# SCH_CheetahSpeedometer-Matt-Lin_2024-07-.net
KiCad netlist of a schematic drawn in EasyEDA
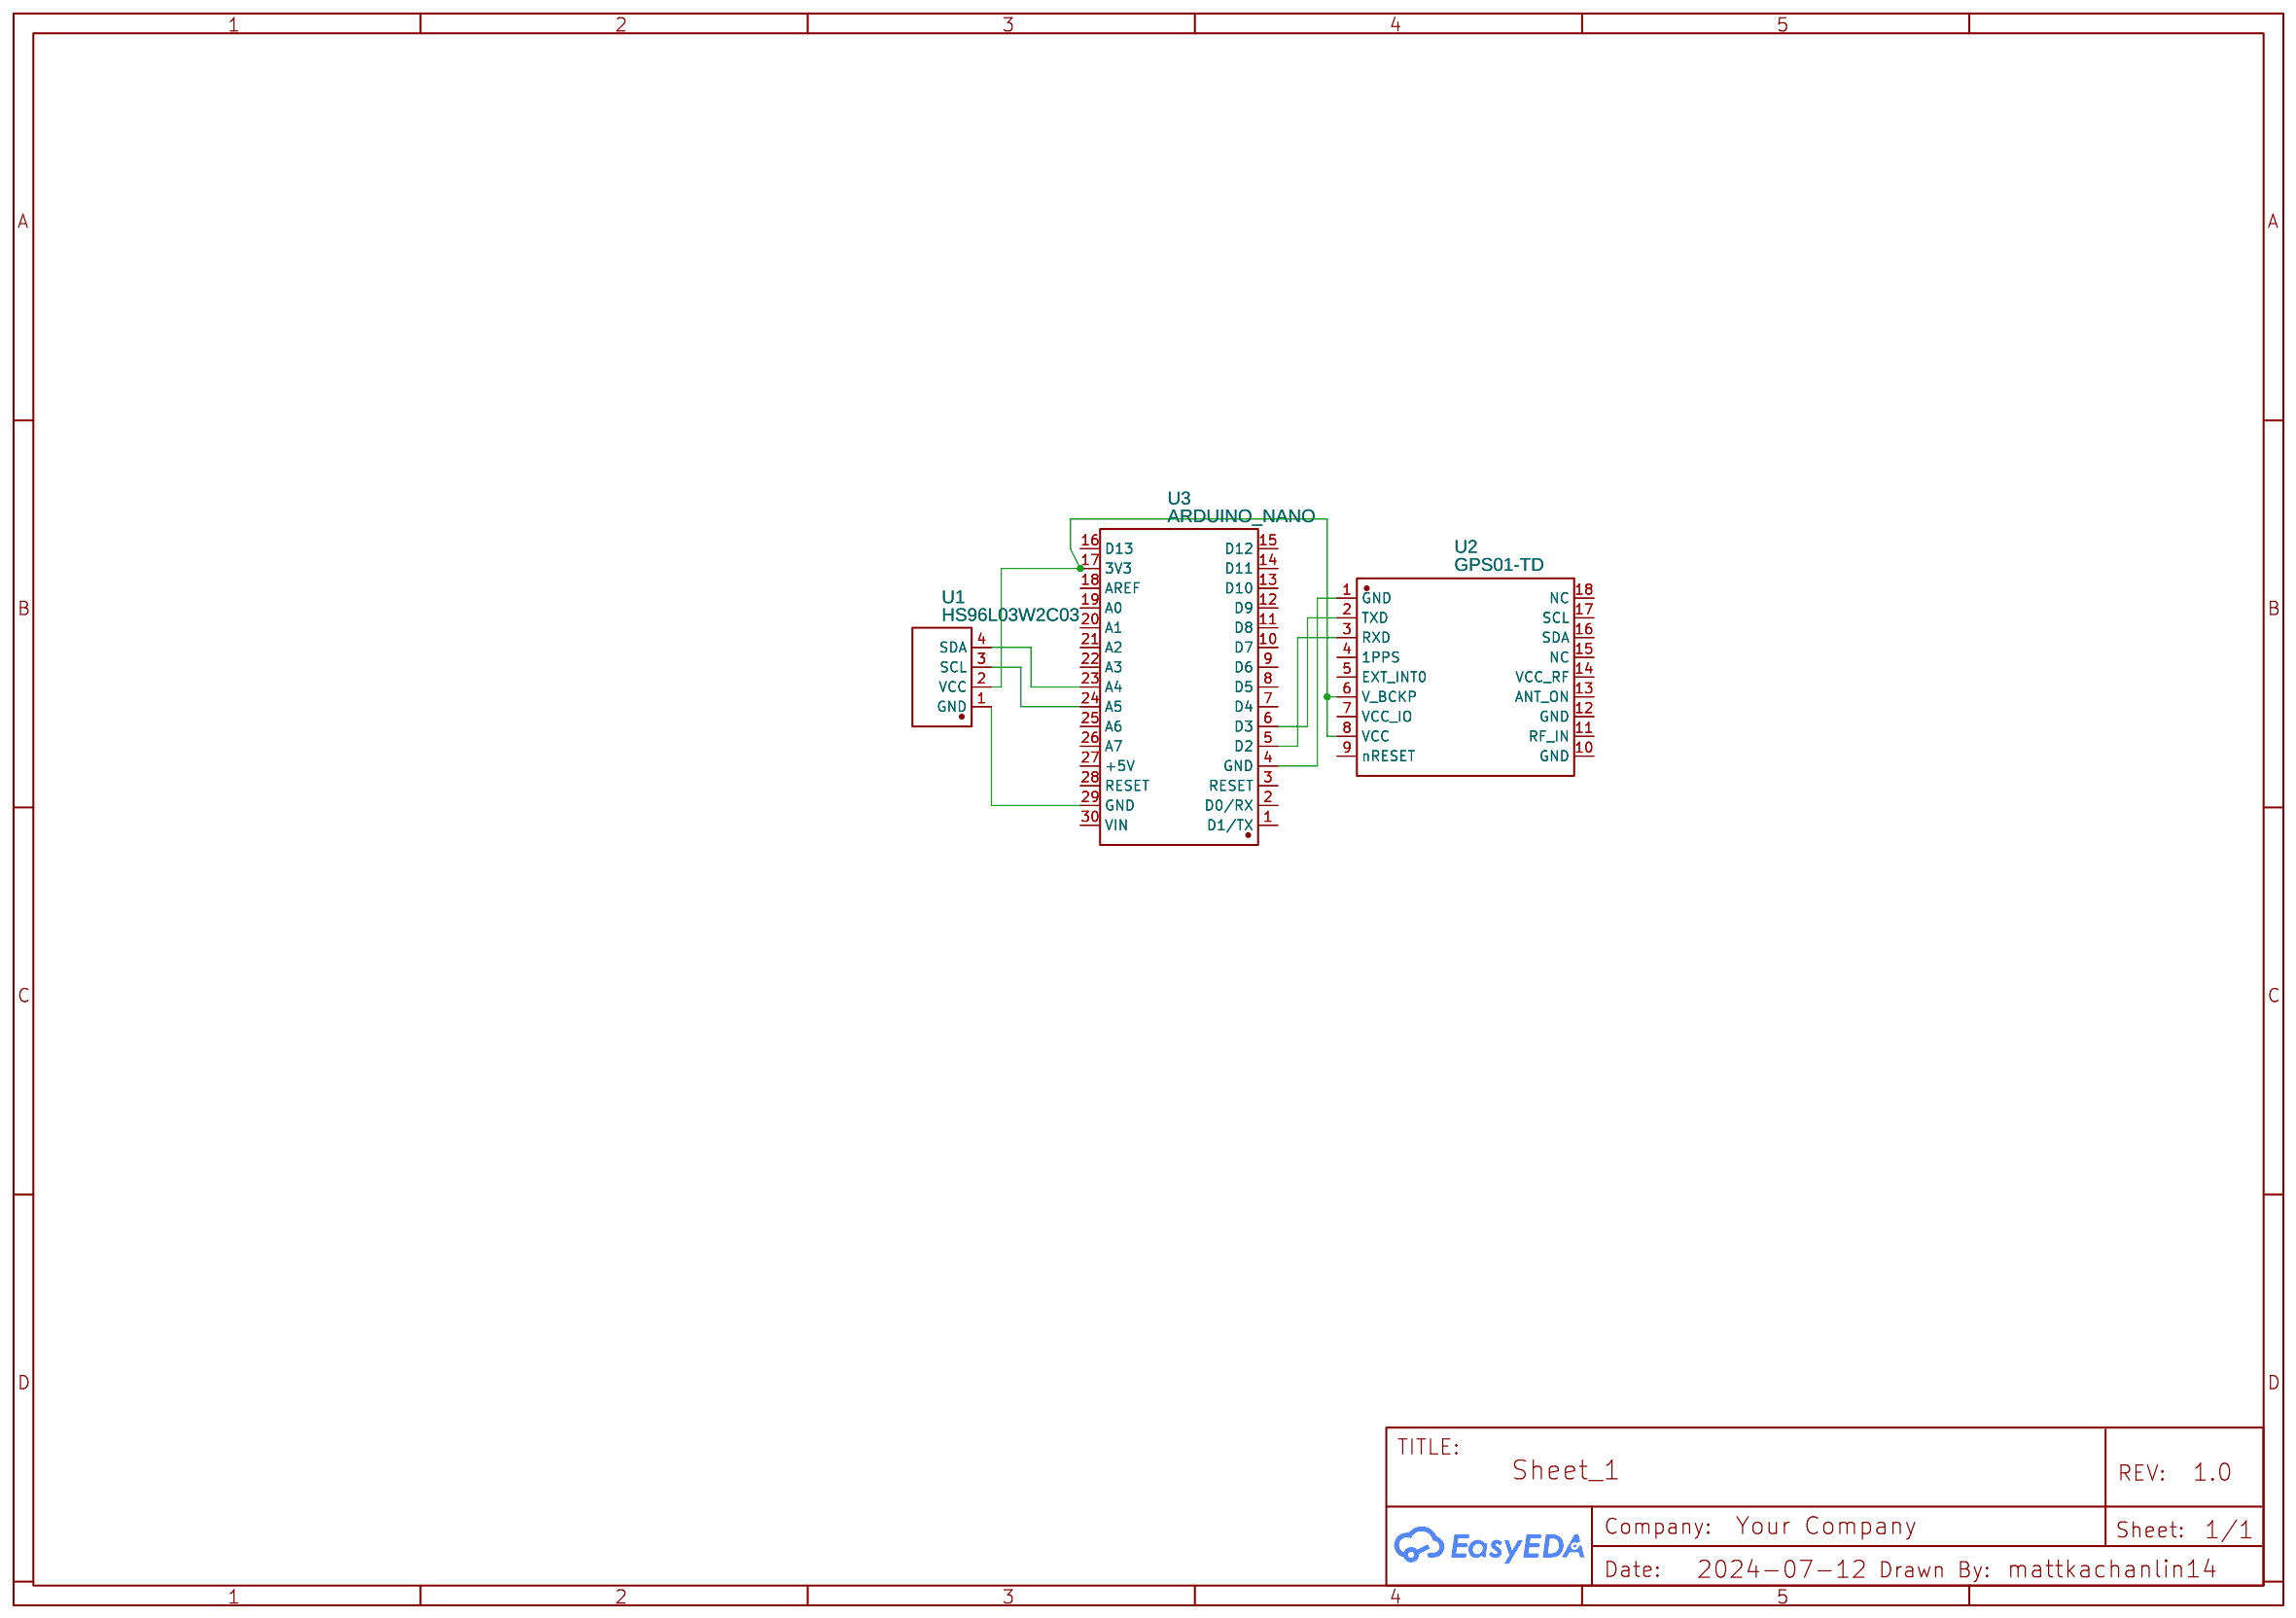
[diagram p0: schematic sheet]

(export (version "E")
  (design (tool "Eeschema 10.0.6"))
  (components
    (comp (ref "U1")
      (value "HS96L03W2C03")
      (fields (field (name "Manufacturer") "HS(汉昇)"))
      (libsource (lib "") (part "HS96L03W2C03"))
    )
    (comp (ref "U2")
      (value "GPS01-TD")
      (fields (field (name "Manufacturer") "G-NiceRF(思为无线)"))
      (libsource (lib "") (part "GPS01-TD"))
    )
    (comp (ref "U3") (value "ARDUINO_NANO") (libsource (lib "") (part "ARDUINO_NANO")))
  )
  (nets
    (net (code "1") (name "Net-(U1-GND)") (class "Default")
      (node (ref "U1") (pin "1") (pinfunction "GND_1") (pintype "unspecified"))
      (node (ref "U3") (pin "29") (pinfunction "GND_29") (pintype "unspecified"))
    )
    (net (code "2") (name "Net-(U1-SCL)") (class "Default")
      (node (ref "U1") (pin "3") (pinfunction "SCL_3") (pintype "unspecified"))
      (node (ref "U3") (pin "24") (pinfunction "A5_24") (pintype "unspecified"))
    )
    (net (code "3") (name "Net-(U1-SDA)") (class "Default")
      (node (ref "U1") (pin "4") (pinfunction "SDA_4") (pintype "unspecified"))
      (node (ref "U3") (pin "23") (pinfunction "A4_23") (pintype "unspecified"))
    )
    (net (code "4") (name "Net-(U1-VCC)") (class "Default")
      (node (ref "U1") (pin "2") (pinfunction "VCC_2") (pintype "unspecified"))
      (node (ref "U2") (pin "6") (pinfunction "V_BCKP_6") (pintype "unspecified"))
      (node (ref "U2") (pin "8") (pinfunction "VCC_8") (pintype "unspecified"))
      (node (ref "U3") (pin "17") (pinfunction "3V3_17") (pintype "unspecified"))
    )
    (net (code "5") (name "Net-(U2-GND-Pad1)") (class "Default")
      (node (ref "U2") (pin "1") (pinfunction "GND_1") (pintype "unspecified"))
      (node (ref "U3") (pin "4") (pinfunction "GND_4") (pintype "unspecified"))
    )
    (net (code "6") (name "Net-(U2-RXD)") (class "Default")
      (node (ref "U2") (pin "3") (pinfunction "RXD_3") (pintype "unspecified"))
      (node (ref "U3") (pin "5") (pinfunction "D2_5") (pintype "unspecified"))
    )
    (net (code "7") (name "Net-(U2-TXD)") (class "Default")
      (node (ref "U2") (pin "2") (pinfunction "TXD_2") (pintype "unspecified"))
      (node (ref "U3") (pin "6") (pinfunction "D3_6") (pintype "unspecified"))
    )
    (net (code "8") (name "unconnected-(U2-1PPS-Pad4)") (class "Default")
      (node (ref "U2") (pin "4") (pinfunction "1PPS_4") (pintype "unspecified"))
    )
    (net (code "9") (name "unconnected-(U2-ANT_ON-Pad13)") (class "Default")
      (node (ref "U2") (pin "13") (pinfunction "ANT_ON_13") (pintype "unspecified"))
    )
    (net (code "10") (name "unconnected-(U2-EXT_INT0-Pad5)") (class "Default")
      (node (ref "U2") (pin "5") (pinfunction "EXT_INT0_5") (pintype "unspecified"))
    )
    (net (code "11") (name "unconnected-(U2-GND-Pad10)") (class "Default")
      (node (ref "U2") (pin "10") (pinfunction "GND_10") (pintype "unspecified"))
    )
    (net (code "12") (name "unconnected-(U2-GND-Pad12)") (class "Default")
      (node (ref "U2") (pin "12") (pinfunction "GND_12") (pintype "unspecified"))
    )
    (net (code "13") (name "unconnected-(U2-NC-Pad15)") (class "Default")
      (node (ref "U2") (pin "15") (pinfunction "NC_15") (pintype "unspecified"))
    )
    (net (code "14") (name "unconnected-(U2-NC-Pad18)") (class "Default")
      (node (ref "U2") (pin "18") (pinfunction "NC_18") (pintype "unspecified"))
    )
    (net (code "15") (name "unconnected-(U2-RF_IN-Pad11)") (class "Default")
      (node (ref "U2") (pin "11") (pinfunction "RF_IN_11") (pintype "unspecified"))
    )
    (net (code "16") (name "unconnected-(U2-SCL-Pad17)") (class "Default")
      (node (ref "U2") (pin "17") (pinfunction "SCL_17") (pintype "unspecified"))
    )
    (net (code "17") (name "unconnected-(U2-SDA-Pad16)") (class "Default")
      (node (ref "U2") (pin "16") (pinfunction "SDA_16") (pintype "unspecified"))
    )
    (net (code "18") (name "unconnected-(U2-VCC_IO-Pad7)") (class "Default")
      (node (ref "U2") (pin "7") (pinfunction "VCC_IO_7") (pintype "unspecified"))
    )
    (net (code "19") (name "unconnected-(U2-VCC_RF-Pad14)") (class "Default")
      (node (ref "U2") (pin "14") (pinfunction "VCC_RF_14") (pintype "unspecified"))
    )
    (net (code "20") (name "unconnected-(U2-nRESET-Pad9)") (class "Default")
      (node (ref "U2") (pin "9") (pinfunction "nRESET_9") (pintype "unspecified"))
    )
    (net (code "21") (name "unconnected-(U3-+5V-Pad27)") (class "Default")
      (node (ref "U3") (pin "27") (pinfunction "+5V_27") (pintype "unspecified"))
    )
    (net (code "22") (name "unconnected-(U3-A0-Pad19)") (class "Default")
      (node (ref "U3") (pin "19") (pinfunction "A0_19") (pintype "unspecified"))
    )
    (net (code "23") (name "unconnected-(U3-A1-Pad20)") (class "Default")
      (node (ref "U3") (pin "20") (pinfunction "A1_20") (pintype "unspecified"))
    )
    (net (code "24") (name "unconnected-(U3-A2-Pad21)") (class "Default")
      (node (ref "U3") (pin "21") (pinfunction "A2_21") (pintype "unspecified"))
    )
    (net (code "25") (name "unconnected-(U3-A3-Pad22)") (class "Default")
      (node (ref "U3") (pin "22") (pinfunction "A3_22") (pintype "unspecified"))
    )
    (net (code "26") (name "unconnected-(U3-A6-Pad25)") (class "Default")
      (node (ref "U3") (pin "25") (pinfunction "A6_25") (pintype "unspecified"))
    )
    (net (code "27") (name "unconnected-(U3-A7-Pad26)") (class "Default")
      (node (ref "U3") (pin "26") (pinfunction "A7_26") (pintype "unspecified"))
    )
    (net (code "28") (name "unconnected-(U3-AREF-Pad18)") (class "Default")
      (node (ref "U3") (pin "18") (pinfunction "AREF_18") (pintype "unspecified"))
    )
    (net (code "29") (name "unconnected-(U3-D0{slash}RX-Pad2)") (class "Default")
      (node (ref "U3") (pin "2") (pinfunction "D0/RX_2") (pintype "unspecified"))
    )
    (net (code "30") (name "unconnected-(U3-D1{slash}TX-Pad1)") (class "Default")
      (node (ref "U3") (pin "1") (pinfunction "D1/TX_1") (pintype "unspecified"))
    )
    (net (code "31") (name "unconnected-(U3-D4-Pad7)") (class "Default")
      (node (ref "U3") (pin "7") (pinfunction "D4_7") (pintype "unspecified"))
    )
    (net (code "32") (name "unconnected-(U3-D5-Pad8)") (class "Default")
      (node (ref "U3") (pin "8") (pinfunction "D5_8") (pintype "unspecified"))
    )
    (net (code "33") (name "unconnected-(U3-D6-Pad9)") (class "Default")
      (node (ref "U3") (pin "9") (pinfunction "D6_9") (pintype "unspecified"))
    )
    (net (code "34") (name "unconnected-(U3-D7-Pad10)") (class "Default")
      (node (ref "U3") (pin "10") (pinfunction "D7_10") (pintype "unspecified"))
    )
    (net (code "35") (name "unconnected-(U3-D8-Pad11)") (class "Default")
      (node (ref "U3") (pin "11") (pinfunction "D8_11") (pintype "unspecified"))
    )
    (net (code "36") (name "unconnected-(U3-D9-Pad12)") (class "Default")
      (node (ref "U3") (pin "12") (pinfunction "D9_12") (pintype "unspecified"))
    )
    (net (code "37") (name "unconnected-(U3-D10-Pad13)") (class "Default")
      (node (ref "U3") (pin "13") (pinfunction "D10_13") (pintype "unspecified"))
    )
    (net (code "38") (name "unconnected-(U3-D11-Pad14)") (class "Default")
      (node (ref "U3") (pin "14") (pinfunction "D11_14") (pintype "unspecified"))
    )
    (net (code "39") (name "unconnected-(U3-D12-Pad15)") (class "Default")
      (node (ref "U3") (pin "15") (pinfunction "D12_15") (pintype "unspecified"))
    )
    (net (code "40") (name "unconnected-(U3-D13-Pad16)") (class "Default")
      (node (ref "U3") (pin "16") (pinfunction "D13_16") (pintype "unspecified"))
    )
    (net (code "41") (name "unconnected-(U3-RESET-Pad3)") (class "Default")
      (node (ref "U3") (pin "3") (pinfunction "RESET_3") (pintype "unspecified"))
    )
    (net (code "42") (name "unconnected-(U3-RESET-Pad28)") (class "Default")
      (node (ref "U3") (pin "28") (pinfunction "RESET_28") (pintype "unspecified"))
    )
    (net (code "43") (name "unconnected-(U3-VIN-Pad30)") (class "Default")
      (node (ref "U3") (pin "30") (pinfunction "VIN_30") (pintype "unspecified"))
    )
  )
)
